# mapleCUx_large_330-014.net
KiCad netlist of a schematic drawn in EAGLE
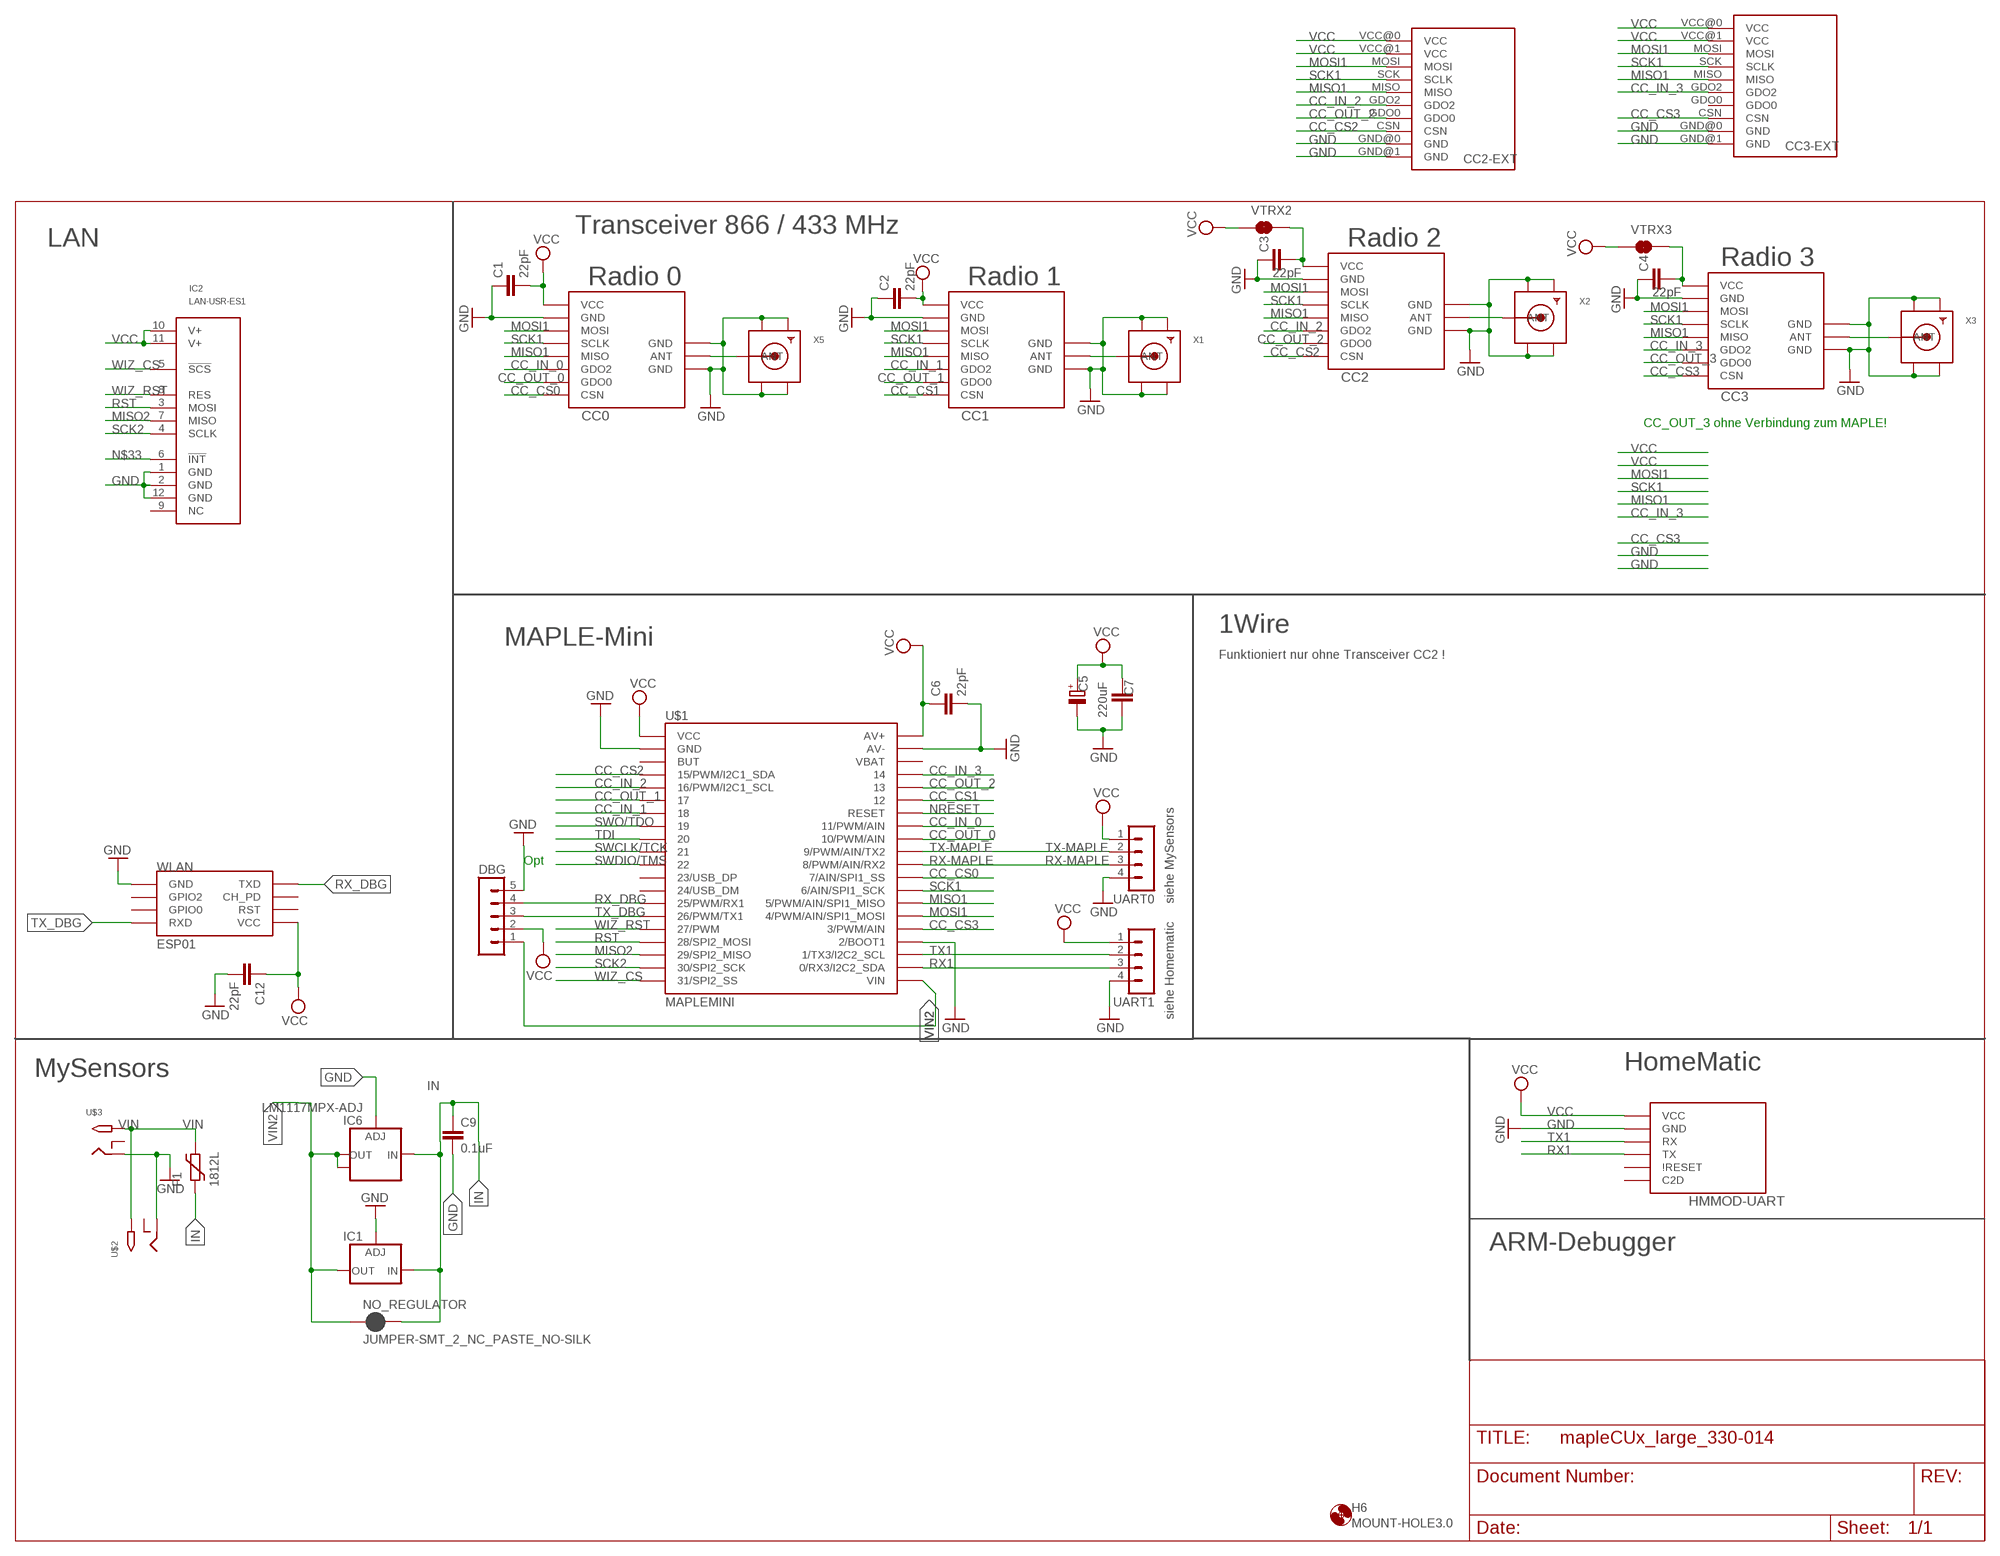
[diagram p0: schematic, sheet 1]

(export (version "E")
  (design (tool "Eeschema 10.0.6"))
  (components
    (comp (ref "C1")
      (value "22pF")
      (footprint "eagle-import:C0805")
      (libsource (lib "eagle-import") (part "C-EUC0805"))
    )
    (comp (ref "C2")
      (value "22pF")
      (footprint "eagle-import:C0805")
      (libsource (lib "eagle-import") (part "C-EUC0805"))
    )
    (comp (ref "C3")
      (value "22pF")
      (footprint "eagle-import:C0805")
      (libsource (lib "eagle-import") (part "C-EUC0805"))
    )
    (comp (ref "C4")
      (value "22pF")
      (footprint "eagle-import:C0805")
      (libsource (lib "eagle-import") (part "C-EUC0805"))
    )
    (comp (ref "C5")
      (value "220uF")
      (footprint "eagle-import:E5-8,5")
      (libsource (lib "eagle-import") (part "CPOL-EUE5-8.5"))
    )
    (comp (ref "C6")
      (value "22pF")
      (footprint "eagle-import:C0805")
      (libsource (lib "eagle-import") (part "C-EUC0805"))
    )
    (comp (ref "C7")
      (value "C-EUC1812")
      (footprint "eagle-import:C1812")
      (libsource (lib "eagle-import") (part "C-EUC1812"))
    )
    (comp (ref "C9")
      (value "0.1uF")
      (footprint "eagle-import:C1206")
      (libsource (lib "eagle-import") (part "C-EUC1206"))
    )
    (comp (ref "C12")
      (value "22pF")
      (footprint "eagle-import:C0805")
      (libsource (lib "eagle-import") (part "C-EUC0805"))
    )
    (comp (ref "CC0")
      (value "CC1101")
      (footprint "eagle-import:CC1101_MODULE1_SMD")
      (libsource (lib "eagle-import") (part "CC1101_MODULE1SMD"))
    )
    (comp (ref "CC1")
      (value "CC1101_MODULE1SMD")
      (footprint "eagle-import:CC1101_MODULE1_SMD")
      (libsource (lib "eagle-import") (part "CC1101_MODULE1SMD"))
    )
    (comp (ref "CC2")
      (value "CC1101_MODULE1SMD")
      (footprint "eagle-import:CC1101_MODULE1_SMD")
      (libsource (lib "eagle-import") (part "CC1101_MODULE1SMD"))
    )
    (comp (ref "CC2-EXT")
      (value "CC1101_MODULE3_DIL")
      (footprint "eagle-import:CC1101_MODULE3_DIL")
      (libsource (lib "eagle-import") (part "CC1101_MODULE3_DIL"))
    )
    (comp (ref "CC3")
      (value "CC1101_MODULE1SMD")
      (footprint "eagle-import:CC1101_MODULE1_SMD")
      (libsource (lib "eagle-import") (part "CC1101_MODULE1SMD"))
    )
    (comp (ref "CC3-EXT")
      (value "CC1101_MODULE3_DIL")
      (footprint "eagle-import:CC1101_MODULE3_DIL")
      (libsource (lib "eagle-import") (part "CC1101_MODULE3_DIL"))
    )
    (comp (ref "DBG")
      (value "MA05-1")
      (footprint "eagle-import:MA05-1")
      (libsource (lib "eagle-import") (part "MA05-1"))
    )
    (comp (ref "F1")
      (value "1812L")
      (footprint "eagle-import:1812L")
      (libsource (lib "eagle-import") (part "1812L"))
    )
    (comp (ref "H6")
      (value "MOUNT-HOLE3.0")
      (footprint "eagle-import:3,0")
      (libsource (lib "eagle-import") (part "MOUNT-HOLE3.0"))
    )
    (comp (ref "HMMOD-UART")
      (value "HM-MOD-UARTDIL")
      (footprint "eagle-import:HM-MOD-UART-DIL")
      (libsource (lib "eagle-import") (part "HM-MOD-UARTDIL"))
    )
    (comp (ref "IC1")
      (value "LD117ADT50TR")
      (footprint "eagle-import:DPACK")
      (libsource (lib "eagle-import") (part "LD117A?DT50TR"))
    )
    (comp (ref "IC2")
      (value "LAN-USR-ES1")
      (footprint "eagle-import:USR-ES1")
      (libsource (lib "eagle-import") (part "LAN-USR-ES1"))
    )
    (comp (ref "IC6")
      (value "LM1117MPX-ADJ")
      (footprint "eagle-import:SOT223")
      (libsource (lib "eagle-import") (part "LM1117MPX-ADJ"))
    )
    (comp (ref "NO_REGULATOR")
      (value "JUMPER-SMT_2_NC_PASTE_NO-SILK")
      (footprint "eagle-import:SMT-JUMPER_2_NC_PASTE_NO-SILK")
      (libsource (lib "eagle-import") (part "JUMPER-SMT_2_NC_PASTE_NO-SILK"))
    )
    (comp (ref "U$1")
      (value "MAPLEMINI")
      (footprint "eagle-import:20-DIP")
      (libsource (lib "eagle-import") (part "MAPLEMINI"))
    )
    (comp (ref "U$2")
      (value "2.1MMJACKTHM")
      (footprint "eagle-import:PJ-102A")
      (libsource (lib "eagle-import") (part "2.1MMJACKTHM"))
    )
    (comp (ref "U$3")
      (value "2.1MMJACKTHM")
      (footprint "eagle-import:PJ-102A")
      (libsource (lib "eagle-import") (part "2.1MMJACKTHM"))
    )
    (comp (ref "UART0")
      (value "MA04-1")
      (footprint "eagle-import:MA04-1")
      (libsource (lib "eagle-import") (part "MA04-1"))
    )
    (comp (ref "UART1")
      (value "MA04-1")
      (footprint "eagle-import:MA04-1")
      (libsource (lib "eagle-import") (part "MA04-1"))
    )
    (comp (ref "VTRX2")
      (value "JUMPER-SMT_2_NC_TRACE_SILK")
      (footprint "eagle-import:SMT-JUMPER_2_NC_TRACE_SILK")
      (libsource (lib "eagle-import") (part "JUMPER-SMT_2_NC_TRACE_SILK"))
    )
    (comp (ref "VTRX3")
      (value "JUMPER-SMT_2_NC_TRACE_SILK")
      (footprint "eagle-import:SMT-JUMPER_2_NC_TRACE_SILK")
      (libsource (lib "eagle-import") (part "JUMPER-SMT_2_NC_TRACE_SILK"))
    )
    (comp (ref "WLAN")
      (value "ESP01")
      (footprint "eagle-import:ESP01")
      (libsource (lib "eagle-import") (part "ESP01"))
    )
    (comp (ref "X1")
      (value "SMACONNECTOR_EDGE")
      (footprint "eagle-import:SMA_EDGELAUNCH")
      (libsource (lib "eagle-import") (part "SMACONNECTOR_EDGE"))
    )
    (comp (ref "X2")
      (value "SMACONNECTOR_EDGE")
      (footprint "eagle-import:SMA_EDGELAUNCH")
      (libsource (lib "eagle-import") (part "SMACONNECTOR_EDGE"))
    )
    (comp (ref "X3")
      (value "SMACONNECTOR_EDGE")
      (footprint "eagle-import:SMA_EDGELAUNCH")
      (libsource (lib "eagle-import") (part "SMACONNECTOR_EDGE"))
    )
    (comp (ref "X5")
      (value "SMACONNECTOR_EDGE")
      (footprint "eagle-import:SMA_EDGELAUNCH")
      (libsource (lib "eagle-import") (part "SMACONNECTOR_EDGE"))
    )
  )
  (nets
    (net (code "1") (name "/CC_CS0") (class "Default")
      (node (ref "CC0") (pin "CSN") (pinfunction "CSN_CSN") (pintype "bidirectional"))
      (node (ref "U$1") (pin "29") (pinfunction "7/AIN/SPI1_SS_29") (pintype "bidirectional"))
    )
    (net (code "2") (name "/CC_CS1") (class "Default")
      (node (ref "CC1") (pin "CSN") (pinfunction "CSN_CSN") (pintype "bidirectional"))
      (node (ref "U$1") (pin "35") (pinfunction "12_35") (pintype "bidirectional"))
    )
    (net (code "3") (name "/CC_CS2") (class "Default")
      (node (ref "CC2") (pin "CSN") (pinfunction "CSN_CSN") (pintype "bidirectional"))
      (node (ref "CC2-EXT") (pin "CSN") (pinfunction "CSN_CSN") (pintype "bidirectional"))
      (node (ref "U$1") (pin "4") (pinfunction "15/PWM/I2C1_SDA_4") (pintype "bidirectional"))
    )
    (net (code "4") (name "/CC_CS3") (class "Default")
      (node (ref "CC3") (pin "CSN") (pinfunction "CSN_CSN") (pintype "bidirectional"))
      (node (ref "CC3-EXT") (pin "CSN") (pinfunction "CSN_CSN") (pintype "bidirectional"))
      (node (ref "U$1") (pin "25") (pinfunction "3/PWM/AIN_25") (pintype "bidirectional"))
    )
    (net (code "5") (name "/CC_IN_0") (class "Default")
      (node (ref "CC0") (pin "GDO2") (pinfunction "GDO2_GDO2") (pintype "bidirectional"))
      (node (ref "U$1") (pin "33") (pinfunction "11/PWM/AIN_33") (pintype "bidirectional"))
    )
    (net (code "6") (name "/CC_IN_1") (class "Default")
      (node (ref "CC1") (pin "GDO2") (pinfunction "GDO2_GDO2") (pintype "bidirectional"))
      (node (ref "U$1") (pin "7") (pinfunction "18_7") (pintype "bidirectional"))
    )
    (net (code "7") (name "/CC_IN_2") (class "Default")
      (node (ref "CC2") (pin "GDO2") (pinfunction "GDO2_GDO2") (pintype "bidirectional"))
      (node (ref "CC2-EXT") (pin "GDO2") (pinfunction "GDO2_GDO2") (pintype "bidirectional"))
      (node (ref "U$1") (pin "5") (pinfunction "16/PWM/I2C1_SCL_5") (pintype "bidirectional"))
    )
    (net (code "8") (name "/CC_IN_3") (class "Default")
      (node (ref "CC3") (pin "GDO2") (pinfunction "GDO2_GDO2") (pintype "bidirectional"))
      (node (ref "CC3-EXT") (pin "GDO2") (pinfunction "GDO2_GDO2") (pintype "bidirectional"))
      (node (ref "U$1") (pin "37") (pinfunction "14_37") (pintype "bidirectional"))
    )
    (net (code "9") (name "/CC_OUT_0") (class "Default")
      (node (ref "CC0") (pin "GDO0") (pinfunction "GDO0_GDO0") (pintype "bidirectional"))
      (node (ref "U$1") (pin "32") (pinfunction "10/PWM/AIN_32") (pintype "bidirectional"))
    )
    (net (code "10") (name "/CC_OUT_1") (class "Default")
      (node (ref "CC1") (pin "GDO0") (pinfunction "GDO0_GDO0") (pintype "bidirectional"))
      (node (ref "U$1") (pin "6") (pinfunction "17_6") (pintype "bidirectional"))
    )
    (net (code "11") (name "/CC_OUT_2") (class "Default")
      (node (ref "CC2") (pin "GDO0") (pinfunction "GDO0_GDO0") (pintype "bidirectional"))
      (node (ref "CC2-EXT") (pin "GDO0") (pinfunction "GDO0_GDO0") (pintype "bidirectional"))
      (node (ref "U$1") (pin "36") (pinfunction "13_36") (pintype "bidirectional"))
    )
    (net (code "12") (name "/CC_OUT_3") (class "Default")
      (node (ref "CC3") (pin "GDO0") (pinfunction "GDO0_GDO0") (pintype "bidirectional"))
    )
    (net (code "13") (name "/MISO1") (class "Default")
      (node (ref "CC0") (pin "MISO") (pinfunction "MISO_MISO") (pintype "bidirectional"))
      (node (ref "CC1") (pin "MISO") (pinfunction "MISO_MISO") (pintype "bidirectional"))
      (node (ref "CC2") (pin "MISO") (pinfunction "MISO_MISO") (pintype "bidirectional"))
      (node (ref "CC2-EXT") (pin "MISO") (pinfunction "MISO_MISO") (pintype "bidirectional"))
      (node (ref "CC3") (pin "MISO") (pinfunction "MISO_MISO") (pintype "bidirectional"))
      (node (ref "CC3-EXT") (pin "MISO") (pinfunction "MISO_MISO") (pintype "bidirectional"))
      (node (ref "U$1") (pin "27") (pinfunction "5/PWM/AIN/SPI1_MISO_27") (pintype "bidirectional"))
    )
    (net (code "14") (name "/MISO2") (class "Default")
      (node (ref "IC2") (pin "7") (pinfunction "MISO_7") (pintype "bidirectional"))
      (node (ref "U$1") (pin "18") (pinfunction "29/SPI2_MISO_18") (pintype "bidirectional"))
    )
    (net (code "15") (name "/MOSI1") (class "Default")
      (node (ref "CC0") (pin "MOSI") (pinfunction "MOSI_MOSI") (pintype "bidirectional"))
      (node (ref "CC1") (pin "MOSI") (pinfunction "MOSI_MOSI") (pintype "bidirectional"))
      (node (ref "CC2") (pin "MOSI") (pinfunction "MOSI_MOSI") (pintype "bidirectional"))
      (node (ref "CC2-EXT") (pin "MOSI") (pinfunction "MOSI_MOSI") (pintype "bidirectional"))
      (node (ref "CC3") (pin "MOSI") (pinfunction "MOSI_MOSI") (pintype "bidirectional"))
      (node (ref "CC3-EXT") (pin "MOSI") (pinfunction "MOSI_MOSI") (pintype "bidirectional"))
      (node (ref "U$1") (pin "26") (pinfunction "4/PWM/AIN/SPI1_MOSI_26") (pintype "bidirectional"))
    )
    (net (code "16") (name "/N$33") (class "Default")
      (node (ref "IC2") (pin "6") (pinfunction "~{INT}_6") (pintype "output"))
    )
    (net (code "17") (name "/NRESET") (class "Default")
      (node (ref "U$1") (pin "34") (pinfunction "RESET_34") (pintype "bidirectional"))
    )
    (net (code "18") (name "/RST") (class "Default")
      (node (ref "IC2") (pin "3") (pinfunction "MOSI_3") (pintype "bidirectional"))
      (node (ref "U$1") (pin "17") (pinfunction "28/SPI2_MOSI_17") (pintype "bidirectional"))
    )
    (net (code "19") (name "/RX-MAPLE") (class "Default")
      (node (ref "U$1") (pin "30") (pinfunction "8/PWM/AIN/RX2_30") (pintype "bidirectional"))
      (node (ref "UART0") (pin "3") (pinfunction "3_3") (pintype "passive"))
    )
    (net (code "20") (name "/RX1") (class "Default")
      (node (ref "HMMOD-UART") (pin "5") (pinfunction "TX_5") (pintype "bidirectional"))
      (node (ref "U$1") (pin "22") (pinfunction "0/RX3/I2C2_SDA_22") (pintype "bidirectional"))
      (node (ref "UART1") (pin "3") (pinfunction "3_3") (pintype "passive"))
    )
    (net (code "21") (name "/SCK1") (class "Default")
      (node (ref "CC0") (pin "SCLK") (pinfunction "SCLK_SCLK") (pintype "bidirectional"))
      (node (ref "CC1") (pin "SCLK") (pinfunction "SCLK_SCLK") (pintype "bidirectional"))
      (node (ref "CC2") (pin "SCLK") (pinfunction "SCLK_SCLK") (pintype "bidirectional"))
      (node (ref "CC2-EXT") (pin "SCK") (pinfunction "SCLK_SCK") (pintype "bidirectional"))
      (node (ref "CC3") (pin "SCLK") (pinfunction "SCLK_SCLK") (pintype "bidirectional"))
      (node (ref "CC3-EXT") (pin "SCK") (pinfunction "SCLK_SCK") (pintype "bidirectional"))
      (node (ref "U$1") (pin "28") (pinfunction "6/AIN/SPI1_SCK_28") (pintype "bidirectional"))
    )
    (net (code "22") (name "/SCK2") (class "Default")
      (node (ref "IC2") (pin "4") (pinfunction "SCLK_4") (pintype "input"))
      (node (ref "U$1") (pin "19") (pinfunction "30/SPI2_SCK_19") (pintype "bidirectional"))
    )
    (net (code "23") (name "/SWCLK{slash}TCK") (class "Default")
      (node (ref "U$1") (pin "10") (pinfunction "21_10") (pintype "bidirectional"))
    )
    (net (code "24") (name "/SWDIO{slash}TMS") (class "Default")
      (node (ref "U$1") (pin "11") (pinfunction "22_11") (pintype "bidirectional"))
    )
    (net (code "25") (name "/SWO{slash}TDO") (class "Default")
      (node (ref "U$1") (pin "8") (pinfunction "19_8") (pintype "bidirectional"))
    )
    (net (code "26") (name "/TDI") (class "Default")
      (node (ref "U$1") (pin "9") (pinfunction "20_9") (pintype "bidirectional"))
    )
    (net (code "27") (name "/TX-MAPLE") (class "Default")
      (node (ref "U$1") (pin "31") (pinfunction "9/PWM/AIN/TX2_31") (pintype "bidirectional"))
      (node (ref "UART0") (pin "2") (pinfunction "2_2") (pintype "passive"))
    )
    (net (code "28") (name "/TX1") (class "Default")
      (node (ref "HMMOD-UART") (pin "6") (pinfunction "RX_6") (pintype "bidirectional"))
      (node (ref "U$1") (pin "23") (pinfunction "1/TX3/I2C2_SCL_23") (pintype "bidirectional"))
      (node (ref "UART1") (pin "2") (pinfunction "2_2") (pintype "passive"))
    )
    (net (code "29") (name "/VIN") (class "Default")
      (node (ref "F1") (pin "P$2") (pinfunction "2_P$2") (pintype "passive"))
      (node (ref "U$2") (pin "TIP") (pinfunction "TIP_TIP") (pintype "bidirectional"))
      (node (ref "U$3") (pin "TIP") (pinfunction "TIP_TIP") (pintype "bidirectional"))
    )
    (net (code "30") (name "/WIZ_CS") (class "Default")
      (node (ref "IC2") (pin "5") (pinfunction "~{SCS}_5") (pintype "input"))
      (node (ref "U$1") (pin "20") (pinfunction "31/SPI2_SS_20") (pintype "bidirectional"))
    )
    (net (code "31") (name "/WIZ_RST") (class "Default")
      (node (ref "IC2") (pin "8") (pinfunction "RES_8") (pintype "input"))
      (node (ref "U$1") (pin "16") (pinfunction "27/PWM_16") (pintype "bidirectional"))
    )
    (net (code "32") (name "GND") (class "Default")
      (node (ref "C1") (pin "1") (pinfunction "1_1") (pintype "passive"))
      (node (ref "C12") (pin "2") (pinfunction "2_2") (pintype "passive"))
      (node (ref "C2") (pin "1") (pinfunction "1_1") (pintype "passive"))
      (node (ref "C3") (pin "1") (pinfunction "1_1") (pintype "passive"))
      (node (ref "C4") (pin "1") (pinfunction "1_1") (pintype "passive"))
      (node (ref "C5") (pin "-") (pinfunction "-_-") (pintype "passive"))
      (node (ref "C6") (pin "2") (pinfunction "2_2") (pintype "passive"))
      (node (ref "C7") (pin "1") (pinfunction "1_1") (pintype "passive"))
      (node (ref "C9") (pin "2") (pinfunction "2_2") (pintype "passive"))
      (node (ref "CC0") (pin "GND@0") (pinfunction "GND_GND@0") (pintype "power_in"))
      (node (ref "CC0") (pin "GND@1") (pinfunction "GND_GND@1") (pintype "power_in"))
      (node (ref "CC0") (pin "GND@2") (pinfunction "GND_GND@2") (pintype "power_in"))
      (node (ref "CC1") (pin "GND@0") (pinfunction "GND_GND@0") (pintype "power_in"))
      (node (ref "CC1") (pin "GND@1") (pinfunction "GND_GND@1") (pintype "power_in"))
      (node (ref "CC1") (pin "GND@2") (pinfunction "GND_GND@2") (pintype "power_in"))
      (node (ref "CC2") (pin "GND@0") (pinfunction "GND_GND@0") (pintype "power_in"))
      (node (ref "CC2") (pin "GND@1") (pinfunction "GND_GND@1") (pintype "power_in"))
      (node (ref "CC2") (pin "GND@2") (pinfunction "GND_GND@2") (pintype "power_in"))
      (node (ref "CC2-EXT") (pin "GND@0") (pinfunction "GND_GND@0") (pintype "power_in"))
      (node (ref "CC2-EXT") (pin "GND@1") (pinfunction "GND_GND@1") (pintype "power_in"))
      (node (ref "CC3") (pin "GND@0") (pinfunction "GND_GND@0") (pintype "power_in"))
      (node (ref "CC3") (pin "GND@1") (pinfunction "GND_GND@1") (pintype "power_in"))
      (node (ref "CC3") (pin "GND@2") (pinfunction "GND_GND@2") (pintype "power_in"))
      (node (ref "CC3-EXT") (pin "GND@0") (pinfunction "GND_GND@0") (pintype "power_in"))
      (node (ref "CC3-EXT") (pin "GND@1") (pinfunction "GND_GND@1") (pintype "power_in"))
      (node (ref "DBG") (pin "5") (pinfunction "5_5") (pintype "passive"))
      (node (ref "HMMOD-UART") (pin "2") (pinfunction "GND_2") (pintype "power_in"))
      (node (ref "IC1") (pin "1") (pinfunction "ADJ_1") (pintype "input"))
      (node (ref "IC2") (pin "1") (pinfunction "GND_1") (pintype "power_in"))
      (node (ref "IC2") (pin "12") (pinfunction "GND_12") (pintype "power_in"))
      (node (ref "IC2") (pin "2") (pinfunction "GND_2") (pintype "power_in"))
      (node (ref "IC6") (pin "1") (pinfunction "ADJ_1") (pintype "input"))
      (node (ref "U$1") (pin "2") (pinfunction "GND_2") (pintype "bidirectional"))
      (node (ref "U$1") (pin "24") (pinfunction "2/BOOT1_24") (pintype "bidirectional"))
      (node (ref "U$1") (pin "39") (pinfunction "AV-_39") (pintype "bidirectional"))
      (node (ref "U$2") (pin "RING") (pinfunction "RING_RING") (pintype "bidirectional"))
      (node (ref "U$3") (pin "RING") (pinfunction "RING_RING") (pintype "bidirectional"))
      (node (ref "UART0") (pin "4") (pinfunction "4_4") (pintype "passive"))
      (node (ref "UART1") (pin "4") (pinfunction "4_4") (pintype "passive"))
      (node (ref "WLAN") (pin "GND") (pinfunction "GND_GND") (pintype "bidirectional"))
      (node (ref "X1") (pin "GND@1") (pinfunction "GND4_GND@1") (pintype "power_in"))
      (node (ref "X1") (pin "GND@2") (pinfunction "GND3_GND@2") (pintype "power_in"))
      (node (ref "X1") (pin "GND@3") (pinfunction "GND2_GND@3") (pintype "power_in"))
      (node (ref "X1") (pin "GND@4") (pinfunction "GND1_GND@4") (pintype "power_in"))
      (node (ref "X2") (pin "GND@1") (pinfunction "GND4_GND@1") (pintype "power_in"))
      (node (ref "X2") (pin "GND@2") (pinfunction "GND3_GND@2") (pintype "power_in"))
      (node (ref "X2") (pin "GND@3") (pinfunction "GND2_GND@3") (pintype "power_in"))
      (node (ref "X2") (pin "GND@4") (pinfunction "GND1_GND@4") (pintype "power_in"))
      (node (ref "X3") (pin "GND@1") (pinfunction "GND4_GND@1") (pintype "power_in"))
      (node (ref "X3") (pin "GND@2") (pinfunction "GND3_GND@2") (pintype "power_in"))
      (node (ref "X3") (pin "GND@3") (pinfunction "GND2_GND@3") (pintype "power_in"))
      (node (ref "X3") (pin "GND@4") (pinfunction "GND1_GND@4") (pintype "power_in"))
      (node (ref "X5") (pin "GND@1") (pinfunction "GND4_GND@1") (pintype "power_in"))
      (node (ref "X5") (pin "GND@2") (pinfunction "GND3_GND@2") (pintype "power_in"))
      (node (ref "X5") (pin "GND@3") (pinfunction "GND2_GND@3") (pintype "power_in"))
      (node (ref "X5") (pin "GND@4") (pinfunction "GND1_GND@4") (pintype "power_in"))
    )
    (net (code "33") (name "IN") (class "Default")
      (node (ref "C9") (pin "1") (pinfunction "1_1") (pintype "passive"))
      (node (ref "F1") (pin "P$1") (pinfunction "1_P$1") (pintype "passive"))
      (node (ref "IC1") (pin "3") (pinfunction "IN_3") (pintype "input"))
      (node (ref "IC6") (pin "3") (pinfunction "IN_3") (pintype "input"))
      (node (ref "NO_REGULATOR") (pin "2") (pinfunction "2_2") (pintype "passive"))
    )
    (net (code "34") (name "Net-(C3-Pad2)") (class "Default")
      (node (ref "C3") (pin "2") (pinfunction "2_2") (pintype "passive"))
      (node (ref "CC2") (pin "VCC") (pinfunction "VCC_VCC") (pintype "power_in"))
      (node (ref "VTRX2") (pin "2") (pinfunction "2_2") (pintype "passive"))
    )
    (net (code "35") (name "Net-(C4-Pad2)") (class "Default")
      (node (ref "C4") (pin "2") (pinfunction "2_2") (pintype "passive"))
      (node (ref "CC3") (pin "VCC") (pinfunction "VCC_VCC") (pintype "power_in"))
      (node (ref "VTRX3") (pin "2") (pinfunction "2_2") (pintype "passive"))
    )
    (net (code "36") (name "Net-(X1-ANT)") (class "Default")
      (node (ref "CC1") (pin "ANT") (pinfunction "ANT_ANT") (pintype "output"))
      (node (ref "X1") (pin "P") (pinfunction "ANT_P") (pintype "bidirectional"))
    )
    (net (code "37") (name "Net-(X2-ANT)") (class "Default")
      (node (ref "CC2") (pin "ANT") (pinfunction "ANT_ANT") (pintype "output"))
      (node (ref "X2") (pin "P") (pinfunction "ANT_P") (pintype "bidirectional"))
    )
    (net (code "38") (name "Net-(X3-ANT)") (class "Default")
      (node (ref "CC3") (pin "ANT") (pinfunction "ANT_ANT") (pintype "output"))
      (node (ref "X3") (pin "P") (pinfunction "ANT_P") (pintype "bidirectional"))
    )
    (net (code "39") (name "Net-(X5-ANT)") (class "Default")
      (node (ref "CC0") (pin "ANT") (pinfunction "ANT_ANT") (pintype "output"))
      (node (ref "X5") (pin "P") (pinfunction "ANT_P") (pintype "bidirectional"))
    )
    (net (code "40") (name "RX_DBG") (class "Default")
      (node (ref "DBG") (pin "4") (pinfunction "4_4") (pintype "passive"))
      (node (ref "U$1") (pin "14") (pinfunction "25/PWM/RX1_14") (pintype "bidirectional"))
      (node (ref "WLAN") (pin "TX") (pinfunction "TXD_TX") (pintype "bidirectional"))
    )
    (net (code "41") (name "TX_DBG") (class "Default")
      (node (ref "DBG") (pin "3") (pinfunction "3_3") (pintype "passive"))
      (node (ref "U$1") (pin "15") (pinfunction "26/PWM/TX1_15") (pintype "bidirectional"))
      (node (ref "WLAN") (pin "RX") (pinfunction "RXD_RX") (pintype "bidirectional"))
    )
    (net (code "42") (name "VCC") (class "Default")
      (node (ref "C1") (pin "2") (pinfunction "2_2") (pintype "passive"))
      (node (ref "C12") (pin "1") (pinfunction "1_1") (pintype "passive"))
      (node (ref "C2") (pin "2") (pinfunction "2_2") (pintype "passive"))
      (node (ref "C5") (pin "+") (pinfunction "+_+") (pintype "passive"))
      (node (ref "C6") (pin "1") (pinfunction "1_1") (pintype "passive"))
      (node (ref "C7") (pin "2") (pinfunction "2_2") (pintype "passive"))
      (node (ref "CC0") (pin "VCC") (pinfunction "VCC_VCC") (pintype "power_in"))
      (node (ref "CC1") (pin "VCC") (pinfunction "VCC_VCC") (pintype "power_in"))
      (node (ref "CC2-EXT") (pin "VCC@0") (pinfunction "VCC_VCC@0") (pintype "power_in"))
      (node (ref "CC2-EXT") (pin "VCC@1") (pinfunction "VCC_VCC@1") (pintype "power_in"))
      (node (ref "CC3-EXT") (pin "VCC@0") (pinfunction "VCC_VCC@0") (pintype "power_in"))
      (node (ref "CC3-EXT") (pin "VCC@1") (pinfunction "VCC_VCC@1") (pintype "power_in"))
      (node (ref "DBG") (pin "2") (pinfunction "2_2") (pintype "passive"))
      (node (ref "HMMOD-UART") (pin "1") (pinfunction "VCC_1") (pintype "power_in"))
      (node (ref "IC2") (pin "10") (pinfunction "V+_10") (pintype "power_in"))
      (node (ref "IC2") (pin "11") (pinfunction "V+_11") (pintype "power_in"))
      (node (ref "U$1") (pin "1") (pinfunction "VCC_1") (pintype "bidirectional"))
      (node (ref "U$1") (pin "40") (pinfunction "AV+_40") (pintype "bidirectional"))
      (node (ref "UART0") (pin "1") (pinfunction "1_1") (pintype "passive"))
      (node (ref "UART1") (pin "1") (pinfunction "1_1") (pintype "passive"))
      (node (ref "VTRX2") (pin "1") (pinfunction "1_1") (pintype "passive"))
      (node (ref "VTRX3") (pin "1") (pinfunction "1_1") (pintype "passive"))
      (node (ref "WLAN") (pin "VCC") (pinfunction "VCC_VCC") (pintype "bidirectional"))
    )
    (net (code "43") (name "VIN2") (class "Default")
      (node (ref "DBG") (pin "1") (pinfunction "1_1") (pintype "passive"))
      (node (ref "IC1") (pin "4") (pinfunction "OUT_4") (pintype "passive"))
      (node (ref "IC6") (pin "2") (pinfunction "OUT_2") (pintype "passive"))
      (node (ref "IC6") (pin "TAB") (pinfunction "OUT1_TAB") (pintype "passive"))
      (node (ref "NO_REGULATOR") (pin "1") (pinfunction "1_1") (pintype "passive"))
      (node (ref "U$1") (pin "21") (pinfunction "VIN_21") (pintype "bidirectional"))
    )
    (net (code "44") (name "unconnected-(CC3-EXT-PadGDO0)") (class "Default")
      (node (ref "CC3-EXT") (pin "GDO0") (pinfunction "GDO0_GDO0") (pintype "bidirectional"))
    )
    (net (code "45") (name "unconnected-(HMMOD-UART-C2D-Pad3)") (class "Default")
      (node (ref "HMMOD-UART") (pin "3") (pinfunction "C2D_3") (pintype "bidirectional"))
    )
    (net (code "46") (name "unconnected-(HMMOD-UART-\\~{RESET}-Pad4)") (class "Default")
      (node (ref "HMMOD-UART") (pin "4") (pinfunction "\\~{RESET}_4") (pintype "bidirectional"))
    )
    (net (code "47") (name "unconnected-(IC2-NC-Pad9)") (class "Default")
      (node (ref "IC2") (pin "9") (pinfunction "NC_9") (pintype "no_connect"))
    )
    (net (code "48") (name "unconnected-(U$1-23{slash}USB_DP-Pad12)") (class "Default")
      (node (ref "U$1") (pin "12") (pinfunction "23/USB_DP_12") (pintype "bidirectional"))
    )
    (net (code "49") (name "unconnected-(U$1-24{slash}USB_DM-Pad13)") (class "Default")
      (node (ref "U$1") (pin "13") (pinfunction "24/USB_DM_13") (pintype "bidirectional"))
    )
    (net (code "50") (name "unconnected-(U$1-BUT-Pad3)") (class "Default")
      (node (ref "U$1") (pin "3") (pinfunction "BUT_3") (pintype "bidirectional"))
    )
    (net (code "51") (name "unconnected-(U$1-VBAT-Pad38)") (class "Default")
      (node (ref "U$1") (pin "38") (pinfunction "VBAT_38") (pintype "bidirectional"))
    )
    (net (code "52") (name "unconnected-(U$2-PadRING_SW)") (class "Default")
      (node (ref "U$2") (pin "RING_SW") (pinfunction "RING_SW_RING_SW") (pintype "bidirectional"))
    )
    (net (code "53") (name "unconnected-(U$3-PadRING_SW)") (class "Default")
      (node (ref "U$3") (pin "RING_SW") (pinfunction "RING_SW_RING_SW") (pintype "bidirectional"))
    )
    (net (code "54") (name "unconnected-(WLAN-PadCH_PD)") (class "Default")
      (node (ref "WLAN") (pin "CH_PD") (pinfunction "CH_PD_CH_PD") (pintype "bidirectional"))
    )
    (net (code "55") (name "unconnected-(WLAN-PadGPIO0)") (class "Default")
      (node (ref "WLAN") (pin "GPIO0") (pinfunction "GPIO0_GPIO0") (pintype "bidirectional"))
    )
    (net (code "56") (name "unconnected-(WLAN-PadGPIO2)") (class "Default")
      (node (ref "WLAN") (pin "GPIO2") (pinfunction "GPIO2_GPIO2") (pintype "bidirectional"))
    )
    (net (code "57") (name "unconnected-(WLAN-PadRST)") (class "Default")
      (node (ref "WLAN") (pin "RST") (pinfunction "RST_RST") (pintype "bidirectional"))
    )
  )
)
